# H01R0_Backend.net
KiCad netlist of a schematic drawn in Altium Designer
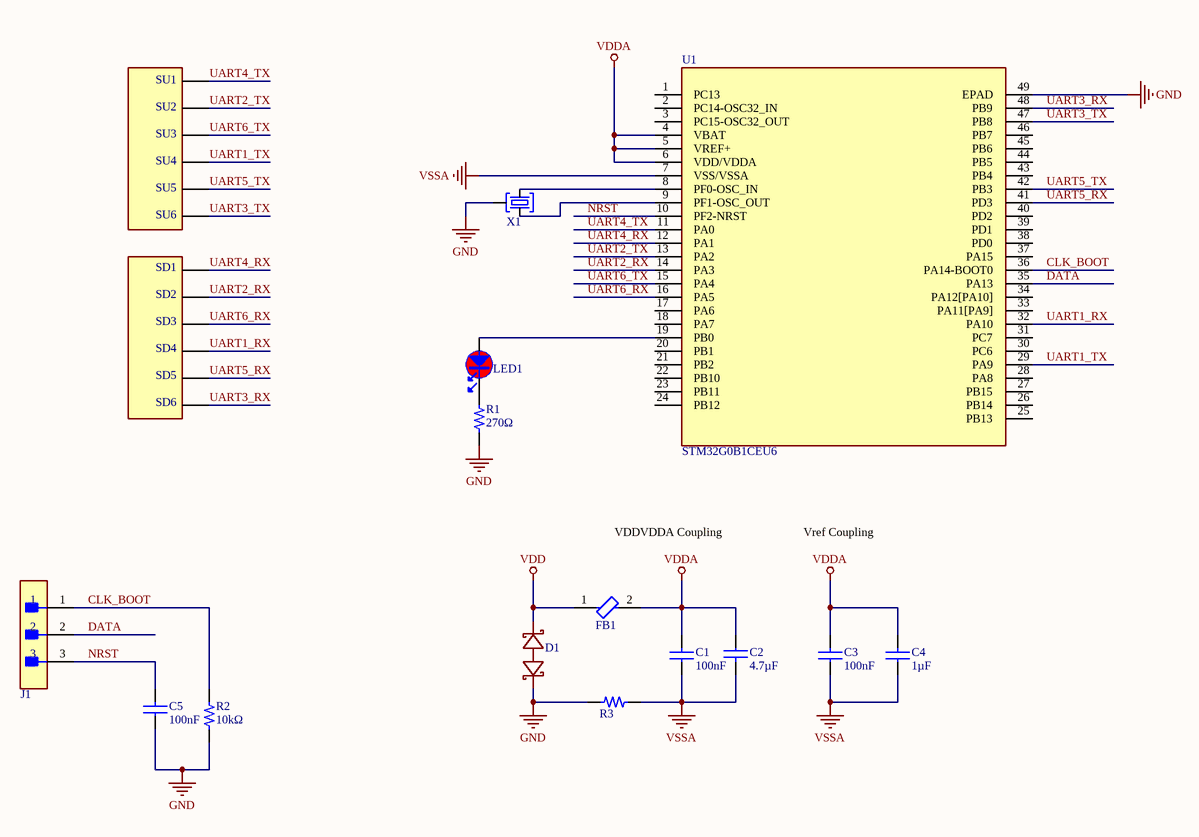
[diagram p0: H01R0_Backend.SchDoc]

(export (version "E")
  (design (tool "Eeschema 10.0.6"))
  (components
    (comp (ref "C1")
      (value "100nF")
      (footprint "C0603")
      (fields
        (field (name "MANUFACTURER") "Samsung Electro-Mechanics")
        (field (name "MANUFACTURER PART NUMBER") "CL10B104KA8NNNC")
        (field (name "TOLERANCE") "10%")
      )
      (libsource (lib "Hexabitz Altium Library") (part "generic Capacitor"))
    )
    (comp (ref "C2")
      (value "4.7µF")
      (footprint "C0805")
      (fields
        (field (name "MANUFACTURER") "Samsung Electro-Mechanics")
        (field (name "MANUFACTURER PART NUMBER") "CL21X475KAQNNNE")
        (field (name "TOLERANCE") "10%")
      )
      (libsource (lib "Hexabitz Altium Library") (part "generic Capacitor"))
    )
    (comp (ref "C3")
      (value "100nF")
      (footprint "C0603")
      (fields
        (field (name "MANUFACTURER") "Samsung Electro-Mechanics")
        (field (name "MANUFACTURER PART NUMBER") "CL10B104KA8NNNC")
        (field (name "TOLERANCE") "10%")
      )
      (libsource (lib "Hexabitz Altium Library") (part "generic Capacitor"))
    )
    (comp (ref "C4")
      (value "1µF")
      (footprint "C0805")
      (description "Ceramic Capacitor, Ceramic, 16V, 10% +Tol, 10% -Tol, X7R, 15% TC, 1uF, Surface Mount, 0805")
      (fields
        (field (name "MANUFACTURER") "Yageo Group")
        (field (name "MANUFACTURER PART NUMBER") "CC0805KKX7R7BB105")
      )
      (libsource (lib "Hexabitz Altium Library") (part "generic Capacitor"))
    )
    (comp (ref "C5")
      (value "100nF")
      (footprint "C0603")
      (fields
        (field (name "MANUFACTURER") "Samsung Electro-Mechanics")
        (field (name "MANUFACTURER PART NUMBER") "CL10B104KA8NNNC")
        (field (name "TOLERANCE") "10%")
      )
      (libsource (lib "Hexabitz Altium Library") (part "generic Capacitor"))
    )
    (comp (ref "D1")
      (value "CDSOD323-T03SC")
      (footprint "SOD2513X114N")
      (description "A 3V, 350W, bi-directional, standard capacitance, SOD323 pkg TVS Diode ¦ Bourns CDSOD323-T03SC")
      (fields (field (name "MANUFACTURER") "Bourns"))
      (libsource (lib "Hexabitz Altium Library") (part "CDSOD323-T03SC"))
    )
    (comp (ref "FB1")
      (value "MMZ1608Y300B")
      (footprint "FP-MMZ1608-0_8-MFG")
      (description "Ferrite Beads 0603 30ohms 1500mA Signal Line AEC-Q200")
      (fields
        (field (name "MANUFACTURER") "TDK")
        (field (name "MANUFACTURER PART NUMBER") "MMZ1608Y300BTD25")
      )
      (libsource (lib "Hexabitz Altium Library") (part "MMZ1608Y300B"))
    )
    (comp (ref "J1")
      (value "TSW-103-14-G-S")
      (footprint "FP-TSW-103-14-G-S-MFG")
      (description "CONN HEADER VERT 3POS 2.54MM")
      (libsource (lib "Altium Content Vault") (part "cd3439d6ef35ae5d9b27ec4fdd3e828"))
    )
    (comp (ref "LED1")
      (value "VLMS1300-GS08")
      (footprint "FP-6_541-5092_01-4-MFG")
      (description "LED Uni-Color Super Red 639nm 2-Pin Chip 0603(1608Metric) T/R")
      (fields (field (name "MANUFACTURER") "Vishay Semiconductors"))
      (libsource (lib "Hexabitz Altium Library") (part "VLMS1300-GS08"))
    )
    (comp (ref "R1")
      (value "270Ω")
      (footprint "R0603")
      (description "Res Thick Film 0603 270 Ohm 5% 0.1W(1/10W) ±200ppm/C Pad SMD Automotive T/R")
      (fields
        (field (name "MANUFACTURER") "Panasonic")
        (field (name "MANUFACTURER PART NUMBER") "ERJ-3GEYJ271V")
      )
      (libsource (lib "") (part "generic Resistor_2"))
    )
    (comp (ref "R2")
      (value "10kΩ")
      (footprint "R0603")
      (description "100mW Thick Film Resistors ±100ppm/℃ ±1% 10kΩ 0603 Chip Resistor - Surface Mount ROHS")
      (fields
        (field (name "MANUFACTURER") "Yageo Group")
        (field (name "MANUFACTURER PART NUMBER") "RC0603FR-0710KL")
      )
      (libsource (lib "Hexabitz Altium Library") (part "generic Resistor"))
    )
    (comp (ref "R3")
      (value "Manufacturer Part Number")
      (footprint "R0603")
      (libsource (lib "") (part "generic Resistor_1"))
    )
    (comp (ref "SD1")
      (value "HEXABIT_UART_PORT")
      (footprint "HEXABIT_UART_PORT_D")
      (libsource (lib "hexabitz_connectors.Library") (part "HEXABIT_UART_PORT_D"))
    )
    (comp (ref "SD2")
      (value "HEXABIT_UART_PORT")
      (footprint "HEXABIT_UART_PORT_D")
      (libsource (lib "hexabitz_connectors.Library") (part "HEXABIT_UART_PORT_D"))
    )
    (comp (ref "SD3")
      (value "HEXABIT_UART_PORT")
      (footprint "HEXABIT_UART_PORT_D")
      (libsource (lib "hexabitz_connectors.Library") (part "HEXABIT_UART_PORT_D"))
    )
    (comp (ref "SD4")
      (value "HEXABIT_UART_PORT")
      (footprint "HEXABIT_UART_PORT_D")
      (libsource (lib "hexabitz_connectors.Library") (part "HEXABIT_UART_PORT_D"))
    )
    (comp (ref "SD5")
      (value "HEXABIT_UART_PORT")
      (footprint "HEXABIT_UART_PORT_D")
      (libsource (lib "hexabitz_connectors.Library") (part "HEXABIT_UART_PORT_D"))
    )
    (comp (ref "SD6")
      (value "HEXABIT_UART_PORT")
      (footprint "HEXABIT_UART_PORT_D")
      (libsource (lib "hexabitz_connectors.Library") (part "HEXABIT_UART_PORT_D"))
    )
    (comp (ref "SU1")
      (value "HEXABIT_UART_PORT")
      (footprint "HEXABIT_UART_PORT_U")
      (libsource (lib "hexabitz_connectors.Library") (part "HEXABIT_UART_PORT_U"))
    )
    (comp (ref "SU2")
      (value "HEXABIT_UART_PORT")
      (footprint "HEXABIT_UART_PORT_U")
      (libsource (lib "hexabitz_connectors.Library") (part "HEXABIT_UART_PORT_U"))
    )
    (comp (ref "SU3")
      (value "HEXABIT_UART_PORT")
      (footprint "HEXABIT_UART_PORT_U")
      (libsource (lib "hexabitz_connectors.Library") (part "HEXABIT_UART_PORT_U"))
    )
    (comp (ref "SU4")
      (value "HEXABIT_UART_PORT")
      (footprint "HEXABIT_UART_PORT_U")
      (libsource (lib "hexabitz_connectors.Library") (part "HEXABIT_UART_PORT_U"))
    )
    (comp (ref "SU5")
      (value "HEXABIT_UART_PORT")
      (footprint "HEXABIT_UART_PORT_U")
      (libsource (lib "hexabitz_connectors.Library") (part "HEXABIT_UART_PORT_U"))
    )
    (comp (ref "SU6")
      (value "HEXABIT_UART_PORT")
      (footprint "HEXABIT_UART_PORT_U")
      (libsource (lib "hexabitz_connectors.Library") (part "HEXABIT_UART_PORT_U"))
    )
    (comp (ref "U1")
      (value "STM32G0B1CEU6")
      (footprint "QFN50P700X700X65-49N-D")
      (description "MCU 32-bit ARM Cortex M0+ RISC 512KB Flash 1.8V/2.5V/3.3V 48-Pin UFQFPN EP Tray")
      (fields
        (field (name "MANUFACTURER") "STMicroelectronics")
        (field (name "MANUFACTURER PART NUMBER") "STM32G0B1CEU6")
      )
      (libsource (lib "Hexabitz Altium Library") (part "STM32G0B1CEU6"))
    )
    (comp (ref "X1")
      (value "CSTCE8M00G52Z-R0")
      (footprint "XTALL_CSTCE8M00G52")
      (description "Ceramic Resonator 8MHz ±0.5% (Tol) ±0.2% (Stability) 10pF 40Ohm 3-Pin CSMD T/R")
      (fields (field (name "MANUFACTURER") "Murata") (field (name "TOLERANCE") "0.5%"))
      (libsource (lib "Hexabitz Altium Library") (part "CSTCE8M00G52Z-R0"))
    )
  )
  (nets
    (net (code "1") (name "/CLK_BOOT") (class "Default")
      (node (ref "J1") (pin "1") (pinfunction "1_1") (pintype "passive"))
      (node (ref "R2") (pin "1") (pinfunction "1_1") (pintype "passive"))
      (node (ref "U1") (pin "36") (pinfunction "PA14-BOOT0_36") (pintype "passive"))
    )
    (net (code "2") (name "/DATA") (class "Default")
      (node (ref "J1") (pin "2") (pinfunction "2_2") (pintype "passive"))
      (node (ref "U1") (pin "35") (pinfunction "PA13_35") (pintype "passive"))
    )
    (net (code "3") (name "/NRST") (class "Default")
      (node (ref "C5") (pin "2") (pinfunction "2_2") (pintype "passive"))
      (node (ref "J1") (pin "3") (pinfunction "3_3") (pintype "passive"))
      (node (ref "U1") (pin "10") (pinfunction "PF2-NRST_10") (pintype "passive"))
    )
    (net (code "4") (name "/UART1_RX") (class "Default")
      (node (ref "SD4") (pin "UART_D") (pinfunction "UART_D_UART_D") (pintype "passive"))
      (node (ref "U1") (pin "32") (pinfunction "PA10_32") (pintype "passive"))
    )
    (net (code "5") (name "/UART1_TX") (class "Default")
      (node (ref "SU4") (pin "UART_U") (pinfunction "UART_U_UART_U") (pintype "passive"))
      (node (ref "U1") (pin "29") (pinfunction "PA9_29") (pintype "passive"))
    )
    (net (code "6") (name "/UART2_RX") (class "Default")
      (node (ref "SD2") (pin "UART_D") (pinfunction "UART_D_UART_D") (pintype "passive"))
      (node (ref "U1") (pin "14") (pinfunction "PA3_14") (pintype "passive"))
    )
    (net (code "7") (name "/UART2_TX") (class "Default")
      (node (ref "SU2") (pin "UART_U") (pinfunction "UART_U_UART_U") (pintype "passive"))
      (node (ref "U1") (pin "13") (pinfunction "PA2_13") (pintype "passive"))
    )
    (net (code "8") (name "/UART3_RX") (class "Default")
      (node (ref "SD6") (pin "UART_D") (pinfunction "UART_D_UART_D") (pintype "passive"))
      (node (ref "U1") (pin "48") (pinfunction "PB9_48") (pintype "passive"))
    )
    (net (code "9") (name "/UART3_TX") (class "Default")
      (node (ref "SU6") (pin "UART_U") (pinfunction "UART_U_UART_U") (pintype "passive"))
      (node (ref "U1") (pin "47") (pinfunction "PB8_47") (pintype "passive"))
    )
    (net (code "10") (name "/UART4_RX") (class "Default")
      (node (ref "SD1") (pin "UART_D") (pinfunction "UART_D_UART_D") (pintype "passive"))
      (node (ref "U1") (pin "12") (pinfunction "PA1_12") (pintype "passive"))
    )
    (net (code "11") (name "/UART4_TX") (class "Default")
      (node (ref "SU1") (pin "UART_U") (pinfunction "UART_U_UART_U") (pintype "passive"))
      (node (ref "U1") (pin "11") (pinfunction "PA0_11") (pintype "passive"))
    )
    (net (code "12") (name "/UART5_RX") (class "Default")
      (node (ref "SD5") (pin "UART_D") (pinfunction "UART_D_UART_D") (pintype "passive"))
      (node (ref "U1") (pin "41") (pinfunction "PD3_41") (pintype "passive"))
    )
    (net (code "13") (name "/UART5_TX") (class "Default")
      (node (ref "SU5") (pin "UART_U") (pinfunction "UART_U_UART_U") (pintype "passive"))
      (node (ref "U1") (pin "42") (pinfunction "PB3_42") (pintype "passive"))
    )
    (net (code "14") (name "/UART6_RX") (class "Default")
      (node (ref "SD3") (pin "UART_D") (pinfunction "UART_D_UART_D") (pintype "passive"))
      (node (ref "U1") (pin "16") (pinfunction "PA5_16") (pintype "passive"))
    )
    (net (code "15") (name "/UART6_TX") (class "Default")
      (node (ref "SU3") (pin "UART_U") (pinfunction "UART_U_UART_U") (pintype "passive"))
      (node (ref "U1") (pin "15") (pinfunction "PA4_15") (pintype "passive"))
    )
    (net (code "16") (name "GND") (class "Default")
      (node (ref "C5") (pin "1") (pinfunction "1_1") (pintype "passive"))
      (node (ref "D1") (pin "1") (pinfunction "A_1") (pintype "passive"))
      (node (ref "R1") (pin "1") (pinfunction "1_1") (pintype "passive"))
      (node (ref "R2") (pin "2") (pinfunction "2_2") (pintype "passive"))
      (node (ref "R3") (pin "1") (pinfunction "1_1") (pintype "passive"))
      (node (ref "U1") (pin "49") (pinfunction "EPAD_49") (pintype "passive"))
      (node (ref "X1") (pin "P$2") (pinfunction "2_P$2") (pintype "passive"))
    )
    (net (code "17") (name "Net-(LED1-Pad1)") (class "Default")
      (node (ref "LED1") (pin "1") (pintype "passive"))
      (node (ref "R1") (pin "2") (pinfunction "2_2") (pintype "passive"))
    )
    (net (code "18") (name "Net-(U1-PB0)") (class "Default")
      (node (ref "LED1") (pin "2") (pintype "passive"))
      (node (ref "U1") (pin "19") (pinfunction "PB0_19") (pintype "passive"))
    )
    (net (code "19") (name "Net-(U1-PF0-OSC_IN)") (class "Default")
      (node (ref "U1") (pin "8") (pinfunction "PF0-OSC_IN_8") (pintype "passive"))
      (node (ref "X1") (pin "P$3") (pinfunction "3_P$3") (pintype "passive"))
    )
    (net (code "20") (name "Net-(U1-PF1-OSC_OUT)") (class "Default")
      (node (ref "U1") (pin "9") (pinfunction "PF1-OSC_OUT_9") (pintype "passive"))
      (node (ref "X1") (pin "P$1") (pinfunction "1_P$1") (pintype "passive"))
    )
    (net (code "21") (name "VDD") (class "Default")
      (node (ref "D1") (pin "2") (pinfunction "C_2") (pintype "passive"))
      (node (ref "FB1") (pin "1") (pinfunction "1_1") (pintype "passive"))
    )
    (net (code "22") (name "VDDA") (class "Default")
      (node (ref "C1") (pin "2") (pinfunction "2_2") (pintype "passive"))
      (node (ref "C2") (pin "1") (pinfunction "1_1") (pintype "passive"))
      (node (ref "C3") (pin "2") (pinfunction "2_2") (pintype "passive"))
      (node (ref "C4") (pin "2") (pinfunction "2_2") (pintype "passive"))
      (node (ref "FB1") (pin "2") (pinfunction "2_2") (pintype "passive"))
      (node (ref "U1") (pin "4") (pinfunction "VBAT_4") (pintype "passive"))
      (node (ref "U1") (pin "5") (pinfunction "VREF+_5") (pintype "passive"))
      (node (ref "U1") (pin "6") (pinfunction "VDD/VDDA_6") (pintype "passive"))
    )
    (net (code "23") (name "VSSA") (class "Default")
      (node (ref "C1") (pin "1") (pinfunction "1_1") (pintype "passive"))
      (node (ref "C2") (pin "2") (pinfunction "2_2") (pintype "passive"))
      (node (ref "C3") (pin "1") (pinfunction "1_1") (pintype "passive"))
      (node (ref "C4") (pin "1") (pinfunction "1_1") (pintype "passive"))
      (node (ref "R3") (pin "2") (pinfunction "2_2") (pintype "passive"))
      (node (ref "U1") (pin "7") (pinfunction "VSS/VSSA_7") (pintype "passive"))
    )
    (net (code "24") (name "unconnected-(U1-PA6-Pad17)") (class "Default")
      (node (ref "U1") (pin "17") (pinfunction "PA6_17") (pintype "passive"))
    )
    (net (code "25") (name "unconnected-(U1-PA7-Pad18)") (class "Default")
      (node (ref "U1") (pin "18") (pinfunction "PA7_18") (pintype "passive"))
    )
    (net (code "26") (name "unconnected-(U1-PA8-Pad28)") (class "Default")
      (node (ref "U1") (pin "28") (pinfunction "PA8_28") (pintype "passive"))
    )
    (net (code "27") (name "unconnected-(U1-PA11[PA9]-Pad33)") (class "Default")
      (node (ref "U1") (pin "33") (pinfunction "PA11[PA9]_33") (pintype "passive"))
    )
    (net (code "28") (name "unconnected-(U1-PA12[PA10]-Pad34)") (class "Default")
      (node (ref "U1") (pin "34") (pinfunction "PA12[PA10]_34") (pintype "passive"))
    )
    (net (code "29") (name "unconnected-(U1-PA15-Pad37)") (class "Default")
      (node (ref "U1") (pin "37") (pinfunction "PA15_37") (pintype "passive"))
    )
    (net (code "30") (name "unconnected-(U1-PB1-Pad20)") (class "Default")
      (node (ref "U1") (pin "20") (pinfunction "PB1_20") (pintype "passive"))
    )
    (net (code "31") (name "unconnected-(U1-PB2-Pad21)") (class "Default")
      (node (ref "U1") (pin "21") (pinfunction "PB2_21") (pintype "passive"))
    )
    (net (code "32") (name "unconnected-(U1-PB4-Pad43)") (class "Default")
      (node (ref "U1") (pin "43") (pinfunction "PB4_43") (pintype "passive"))
    )
    (net (code "33") (name "unconnected-(U1-PB5-Pad44)") (class "Default")
      (node (ref "U1") (pin "44") (pinfunction "PB5_44") (pintype "passive"))
    )
    (net (code "34") (name "unconnected-(U1-PB6-Pad45)") (class "Default")
      (node (ref "U1") (pin "45") (pinfunction "PB6_45") (pintype "passive"))
    )
    (net (code "35") (name "unconnected-(U1-PB7-Pad46)") (class "Default")
      (node (ref "U1") (pin "46") (pinfunction "PB7_46") (pintype "passive"))
    )
    (net (code "36") (name "unconnected-(U1-PB10-Pad22)") (class "Default")
      (node (ref "U1") (pin "22") (pinfunction "PB10_22") (pintype "passive"))
    )
    (net (code "37") (name "unconnected-(U1-PB11-Pad23)") (class "Default")
      (node (ref "U1") (pin "23") (pinfunction "PB11_23") (pintype "passive"))
    )
    (net (code "38") (name "unconnected-(U1-PB12-Pad24)") (class "Default")
      (node (ref "U1") (pin "24") (pinfunction "PB12_24") (pintype "passive"))
    )
    (net (code "39") (name "unconnected-(U1-PB13-Pad25)") (class "Default")
      (node (ref "U1") (pin "25") (pinfunction "PB13_25") (pintype "passive"))
    )
    (net (code "40") (name "unconnected-(U1-PB14-Pad26)") (class "Default")
      (node (ref "U1") (pin "26") (pinfunction "PB14_26") (pintype "passive"))
    )
    (net (code "41") (name "unconnected-(U1-PB15-Pad27)") (class "Default")
      (node (ref "U1") (pin "27") (pinfunction "PB15_27") (pintype "passive"))
    )
    (net (code "42") (name "unconnected-(U1-PC6-Pad30)") (class "Default")
      (node (ref "U1") (pin "30") (pinfunction "PC6_30") (pintype "passive"))
    )
    (net (code "43") (name "unconnected-(U1-PC7-Pad31)") (class "Default")
      (node (ref "U1") (pin "31") (pinfunction "PC7_31") (pintype "passive"))
    )
    (net (code "44") (name "unconnected-(U1-PC13-Pad1)") (class "Default")
      (node (ref "U1") (pin "1") (pinfunction "PC13_1") (pintype "passive"))
    )
    (net (code "45") (name "unconnected-(U1-PC14-OSC32_IN-Pad2)") (class "Default")
      (node (ref "U1") (pin "2") (pinfunction "PC14-OSC32_IN_2") (pintype "passive"))
    )
    (net (code "46") (name "unconnected-(U1-PC15-OSC32_OUT-Pad3)") (class "Default")
      (node (ref "U1") (pin "3") (pinfunction "PC15-OSC32_OUT_3") (pintype "passive"))
    )
    (net (code "47") (name "unconnected-(U1-PD0-Pad38)") (class "Default")
      (node (ref "U1") (pin "38") (pinfunction "PD0_38") (pintype "passive"))
    )
    (net (code "48") (name "unconnected-(U1-PD1-Pad39)") (class "Default")
      (node (ref "U1") (pin "39") (pinfunction "PD1_39") (pintype "passive"))
    )
    (net (code "49") (name "unconnected-(U1-PD2-Pad40)") (class "Default")
      (node (ref "U1") (pin "40") (pinfunction "PD2_40") (pintype "passive"))
    )
  )
)
